# arduino_uno_to_attiny_x5.net
KiCad netlist of a schematic drawn in EAGLE
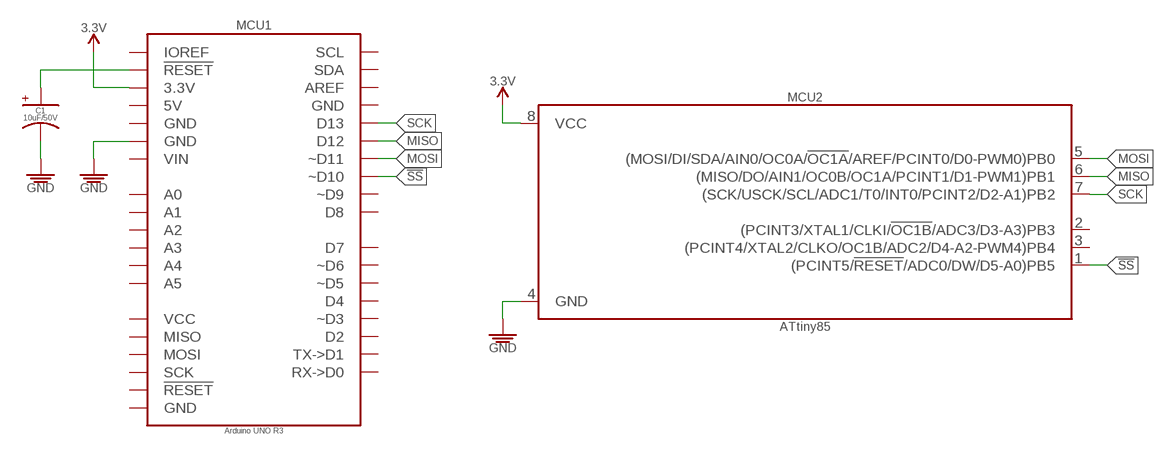
[diagram p0: schematic, sheet 1]

(export (version "E")
  (design (tool "Eeschema 10.0.6"))
  (components
    (comp (ref "C1")
      (value "10uF/50V")
      (footprint "eagle-import:_AE_PTH-DIA5-LS2-H5")
      (fields (field (name "MFR") "Panasonic Electronic Components") (field (name "MPN") "ECE-A1HKA100"))
      (libsource (lib "eagle-import") (part "10UF-POLARIZED_PTH_50V-20%"))
    )
    (comp (ref "MCU1")
      (value "Arduino UNO R3")
      (footprint "eagle-import:ARDUINO_UNO_R3")
      (fields (field (name "MFR") "Arduino") (field (name "MPN") "A000066"))
      (libsource (lib "eagle-import") (part "ARDUINO_UNO_R3"))
    )
    (comp (ref "MCU2")
      (value "ATtiny85")
      (footprint "eagle-import:DIP787W45P254L958H533Q8B_DIP-8_ATTINY-X5")
      (fields
        (field (name "MFR") "Microchip Technology")
        (field (name "MPN") "ATTINY85-20PU")
        (field (name "SPICEPREFIX") "X")
      )
      (libsource (lib "eagle-import") (part "ATTINY-X5_DIP-8_ATTINY-85"))
    )
  )
  (nets
    (net (code "1") (name "/~{SS}") (class "Default")
      (node (ref "MCU1") (pin "D10") (pinfunction "~{D10}_D10") (pintype "bidirectional"))
      (node (ref "MCU2") (pin "1") (pinfunction "(PCINT5/~{RESET}/ADC0/DW/D5-A0)PB5_1") (pintype "bidirectional"))
    )
    (net (code "2") (name "3.3V") (class "Default")
      (node (ref "MCU1") (pin "3.3V") (pinfunction "3.3V_3.3V") (pintype "bidirectional"))
      (node (ref "MCU2") (pin "8") (pinfunction "VCC_8") (pintype "power_in"))
    )
    (net (code "3") (name "GND") (class "Default")
      (node (ref "C1") (pin "-") (pinfunction "K_-") (pintype "passive"))
      (node (ref "MCU1") (pin "GND@3") (pinfunction "GND_GND@3") (pintype "bidirectional"))
      (node (ref "MCU2") (pin "4") (pinfunction "GND_4") (pintype "power_in"))
    )
    (net (code "4") (name "MISO") (class "Default")
      (node (ref "MCU1") (pin "D12") (pinfunction "D12_D12") (pintype "bidirectional"))
      (node (ref "MCU2") (pin "6") (pinfunction "(MISO/DO/AIN1/OC0B/OC1A/PCINT1/D1-PWM1)PB1_6") (pintype "bidirectional"))
    )
    (net (code "5") (name "MOSI") (class "Default")
      (node (ref "MCU1") (pin "D11") (pinfunction "~{D11}_D11") (pintype "bidirectional"))
      (node (ref "MCU2") (pin "5") (pinfunction "(MOSI/DI/SDA/AIN0/OC0A/~{OC1A}/AREF/PCINT0/D0-PWM0)PB0_5") (pintype "bidirectional"))
    )
    (net (code "6") (name "Net-(C1-A)") (class "Default")
      (node (ref "C1") (pin "+") (pinfunction "A_+") (pintype "passive"))
      (node (ref "MCU1") (pin "RESET@1") (pinfunction "~{RESET}_RESET@1") (pintype "bidirectional"))
    )
    (net (code "7") (name "SCK") (class "Default")
      (node (ref "MCU1") (pin "D13") (pinfunction "D13_D13") (pintype "bidirectional"))
      (node (ref "MCU2") (pin "7") (pinfunction "(SCK/USCK/SCL/ADC1/T0/INT0/PCINT2/D2-A1)PB2_7") (pintype "bidirectional"))
    )
    (net (code "8") (name "unconnected-(MCU1-GND-PadGND@1)") (class "Default")
      (node (ref "MCU1") (pin "GND@1") (pinfunction "GND_GND@1") (pintype "bidirectional"))
    )
    (net (code "9") (name "unconnected-(MCU1-GND-PadGND@2)") (class "Default")
      (node (ref "MCU1") (pin "GND@2") (pinfunction "GND_GND@2") (pintype "bidirectional"))
    )
    (net (code "10") (name "unconnected-(MCU1-GND-PadGND@4)") (class "Default")
      (node (ref "MCU1") (pin "GND@4") (pinfunction "GND_GND@4") (pintype "bidirectional"))
    )
    (net (code "11") (name "unconnected-(MCU1-Pad5V)") (class "Default")
      (node (ref "MCU1") (pin "5V") (pinfunction "5V_5V") (pintype "bidirectional"))
    )
    (net (code "12") (name "unconnected-(MCU1-PadA0)") (class "Default")
      (node (ref "MCU1") (pin "A0") (pinfunction "A0_A0") (pintype "bidirectional"))
    )
    (net (code "13") (name "unconnected-(MCU1-PadA1)") (class "Default")
      (node (ref "MCU1") (pin "A1") (pinfunction "A1_A1") (pintype "bidirectional"))
    )
    (net (code "14") (name "unconnected-(MCU1-PadA2)") (class "Default")
      (node (ref "MCU1") (pin "A2") (pinfunction "A2_A2") (pintype "bidirectional"))
    )
    (net (code "15") (name "unconnected-(MCU1-PadA3)") (class "Default")
      (node (ref "MCU1") (pin "A3") (pinfunction "A3_A3") (pintype "bidirectional"))
    )
    (net (code "16") (name "unconnected-(MCU1-PadA4)") (class "Default")
      (node (ref "MCU1") (pin "A4") (pinfunction "A4_A4") (pintype "bidirectional"))
    )
    (net (code "17") (name "unconnected-(MCU1-PadA5)") (class "Default")
      (node (ref "MCU1") (pin "A5") (pinfunction "A5_A5") (pintype "bidirectional"))
    )
    (net (code "18") (name "unconnected-(MCU1-PadAREF)") (class "Default")
      (node (ref "MCU1") (pin "AREF") (pinfunction "AREF_AREF") (pintype "bidirectional"))
    )
    (net (code "19") (name "unconnected-(MCU1-PadD2)") (class "Default")
      (node (ref "MCU1") (pin "D2") (pinfunction "D2_D2") (pintype "bidirectional"))
    )
    (net (code "20") (name "unconnected-(MCU1-PadD4)") (class "Default")
      (node (ref "MCU1") (pin "D4") (pinfunction "D4_D4") (pintype "bidirectional"))
    )
    (net (code "21") (name "unconnected-(MCU1-PadD7)") (class "Default")
      (node (ref "MCU1") (pin "D7") (pinfunction "D7_D7") (pintype "bidirectional"))
    )
    (net (code "22") (name "unconnected-(MCU1-PadD8)") (class "Default")
      (node (ref "MCU1") (pin "D8") (pinfunction "D8_D8") (pintype "bidirectional"))
    )
    (net (code "23") (name "unconnected-(MCU1-PadIOREF)") (class "Default")
      (node (ref "MCU1") (pin "IOREF") (pinfunction "IOREF_IOREF") (pintype "bidirectional"))
    )
    (net (code "24") (name "unconnected-(MCU1-PadMISO)") (class "Default")
      (node (ref "MCU1") (pin "MISO") (pinfunction "MISO_MISO") (pintype "bidirectional"))
    )
    (net (code "25") (name "unconnected-(MCU1-PadMOSI)") (class "Default")
      (node (ref "MCU1") (pin "MOSI") (pinfunction "MOSI_MOSI") (pintype "bidirectional"))
    )
    (net (code "26") (name "unconnected-(MCU1-PadSCK)") (class "Default")
      (node (ref "MCU1") (pin "SCK") (pinfunction "SCK_SCK") (pintype "bidirectional"))
    )
    (net (code "27") (name "unconnected-(MCU1-PadSCL)") (class "Default")
      (node (ref "MCU1") (pin "SCL") (pinfunction "SCL_SCL") (pintype "bidirectional"))
    )
    (net (code "28") (name "unconnected-(MCU1-PadSDA)") (class "Default")
      (node (ref "MCU1") (pin "SDA") (pinfunction "SDA_SDA") (pintype "bidirectional"))
    )
    (net (code "29") (name "unconnected-(MCU1-PadVCC)") (class "Default")
      (node (ref "MCU1") (pin "VCC") (pinfunction "VCC_VCC") (pintype "bidirectional"))
    )
    (net (code "30") (name "unconnected-(MCU1-PadVIN)") (class "Default")
      (node (ref "MCU1") (pin "VIN") (pinfunction "VIN_VIN") (pintype "bidirectional"))
    )
    (net (code "31") (name "unconnected-(MCU1-RX->D0-PadD0)") (class "Default")
      (node (ref "MCU1") (pin "D0") (pinfunction "RX->D0_D0") (pintype "bidirectional"))
    )
    (net (code "32") (name "unconnected-(MCU1-TX->D1-PadD1)") (class "Default")
      (node (ref "MCU1") (pin "D1") (pinfunction "TX->D1_D1") (pintype "bidirectional"))
    )
    (net (code "33") (name "unconnected-(MCU1-~{D3}-PadD3)") (class "Default")
      (node (ref "MCU1") (pin "D3") (pinfunction "~{D3}_D3") (pintype "bidirectional"))
    )
    (net (code "34") (name "unconnected-(MCU1-~{D5}-PadD5)") (class "Default")
      (node (ref "MCU1") (pin "D5") (pinfunction "~{D5}_D5") (pintype "bidirectional"))
    )
    (net (code "35") (name "unconnected-(MCU1-~{D6}-PadD6)") (class "Default")
      (node (ref "MCU1") (pin "D6") (pinfunction "~{D6}_D6") (pintype "bidirectional"))
    )
    (net (code "36") (name "unconnected-(MCU1-~{D9}-PadD9)") (class "Default")
      (node (ref "MCU1") (pin "D9") (pinfunction "~{D9}_D9") (pintype "bidirectional"))
    )
    (net (code "37") (name "unconnected-(MCU1-~{RESET}-PadRESET@2)") (class "Default")
      (node (ref "MCU1") (pin "RESET@2") (pinfunction "~{RESET}_RESET@2") (pintype "bidirectional"))
    )
    (net (code "38") (name "unconnected-(MCU2-(PCINT3{slash}XTAL1{slash}CLKI{slash}~{OC1B}{slash}ADC3{slash}D3-A3)PB3-Pad2)") (class "Default")
      (node (ref "MCU2") (pin "2") (pinfunction "(PCINT3/XTAL1/CLKI/~{OC1B}/ADC3/D3-A3)PB3_2") (pintype "bidirectional"))
    )
    (net (code "39") (name "unconnected-(MCU2-(PCINT4{slash}XTAL2{slash}CLKO{slash}OC1B{slash}ADC2{slash}D4-A2-PWM4)PB4-Pad3)") (class "Default")
      (node (ref "MCU2") (pin "3") (pinfunction "(PCINT4/XTAL2/CLKO/OC1B/ADC2/D4-A2-PWM4)PB4_3") (pintype "bidirectional"))
    )
  )
)
